# RFM2Pi_K16.net
KiCad netlist of a schematic drawn in EAGLE
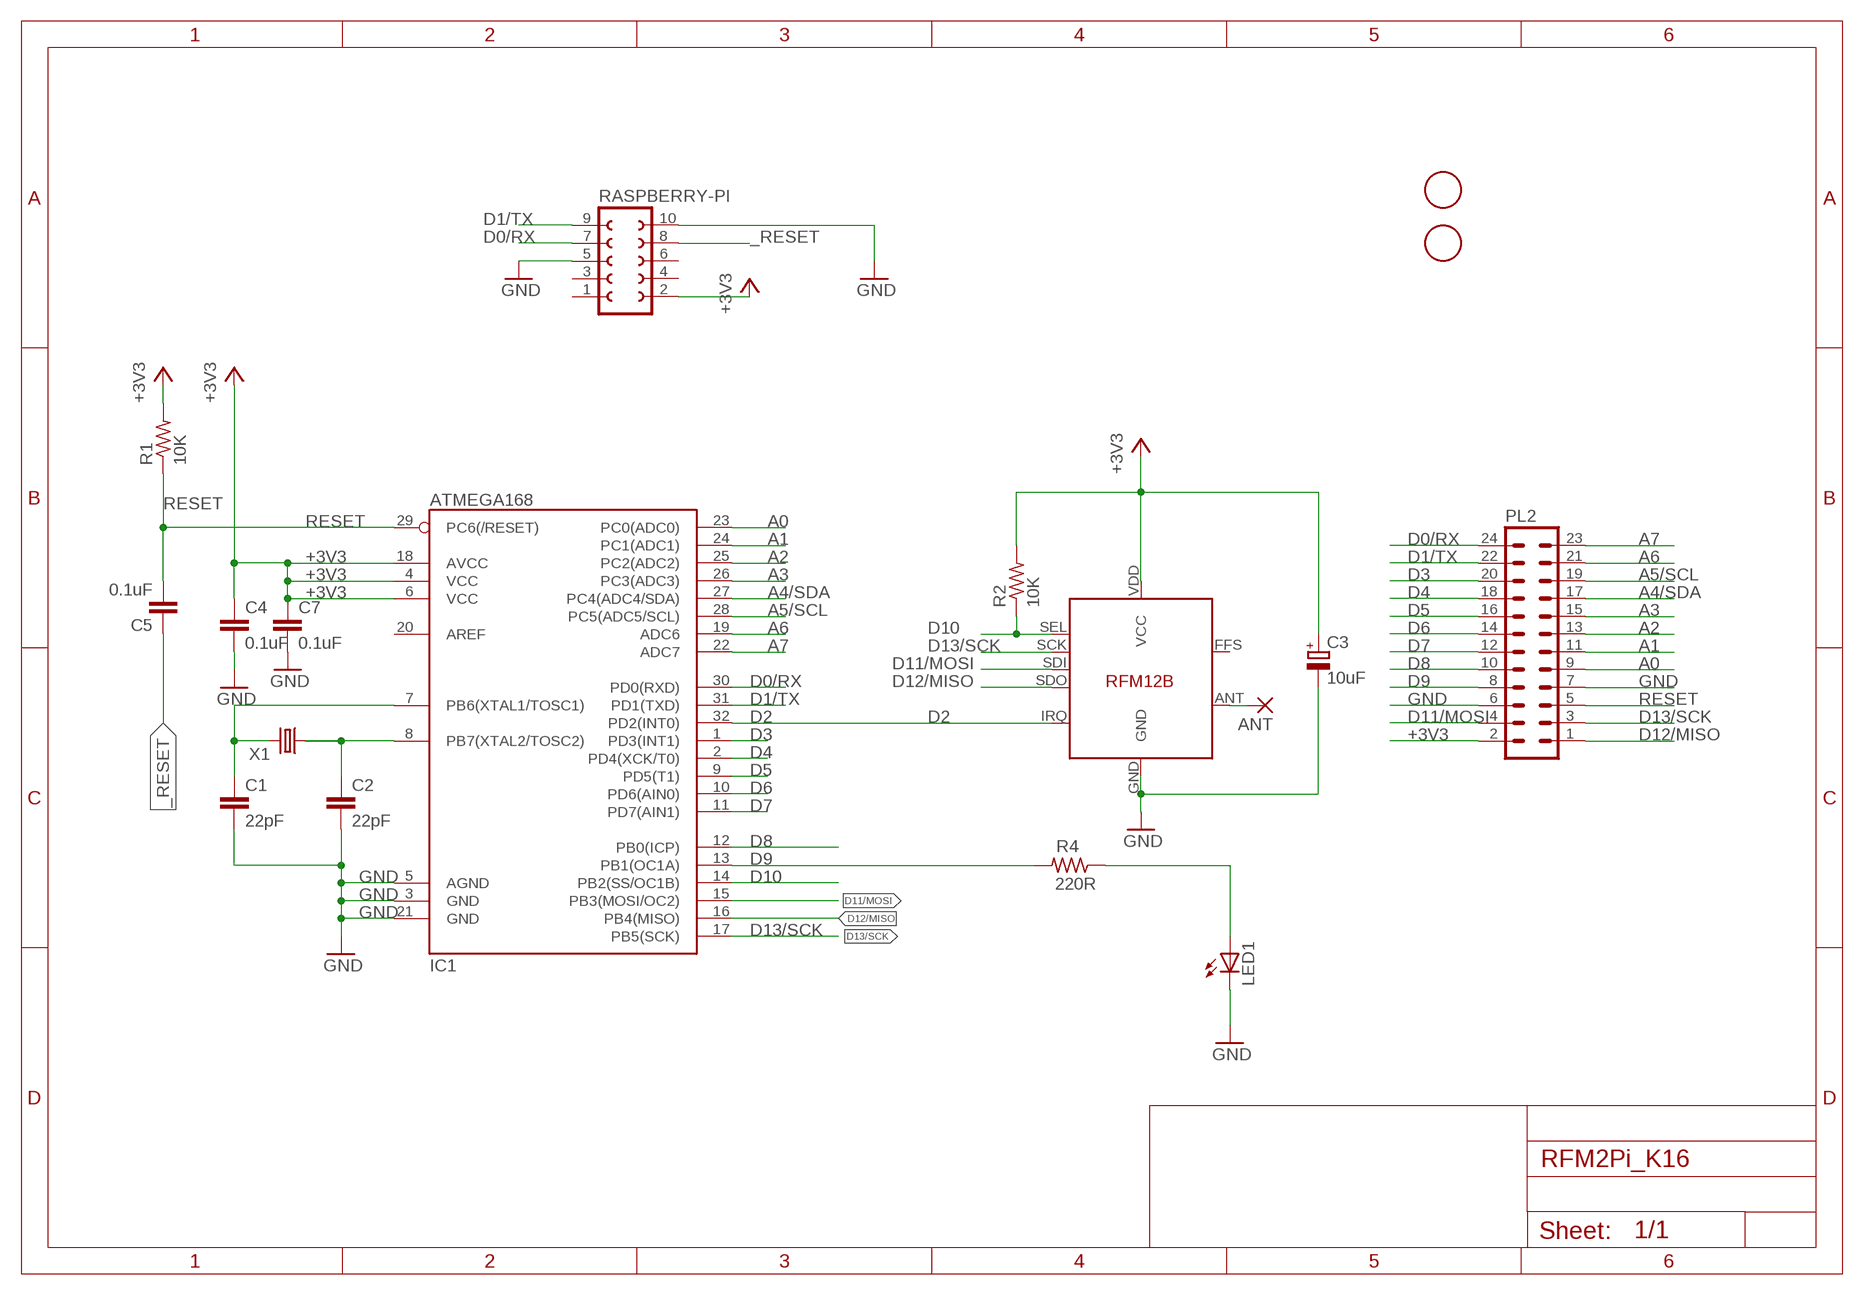
[diagram p0: schematic, sheet 1]

(export (version "E")
  (design (tool "Eeschema 10.0.6"))
  (components
    (comp (ref "ANT")
      (value "1,6/0,8")
      (footprint "eagle-import:1,6_0,8")
      (libsource (lib "eagle-import") (part "1,6/0,8"))
    )
    (comp (ref "C1")
      (value "22pF")
      (footprint "eagle-import:C0603")
      (libsource (lib "eagle-import") (part "C-EUC0603"))
    )
    (comp (ref "C2")
      (value "22pF")
      (footprint "eagle-import:C0603")
      (libsource (lib "eagle-import") (part "C-EUC0603"))
    )
    (comp (ref "C3")
      (value "10uF")
      (footprint "eagle-import:B_3528-21W")
      (libsource (lib "eagle-import") (part "CPOL-EUB/3528-21W"))
    )
    (comp (ref "C4")
      (value "0.1uF")
      (footprint "eagle-import:C0603")
      (libsource (lib "eagle-import") (part "C-EUC0603"))
    )
    (comp (ref "C5")
      (value "0.1uF")
      (footprint "eagle-import:C0603")
      (libsource (lib "eagle-import") (part "C-EUC0603"))
    )
    (comp (ref "C7")
      (value "0.1uF")
      (footprint "eagle-import:C0603")
      (libsource (lib "eagle-import") (part "resistor_C-EUC0603"))
    )
    (comp (ref "IC1")
      (value "ATMEGA168")
      (footprint "eagle-import:TQFP32-08")
      (libsource (lib "eagle-import") (part "ATMEGA168"))
    )
    (comp (ref "LED1")
      (value "LEDSML0603")
      (footprint "eagle-import:SML0603")
      (libsource (lib "eagle-import") (part "LEDSML0603"))
    )
    (comp (ref "PL2")
      (value "MA12-2")
      (footprint "eagle-import:MA12-2")
      (libsource (lib "eagle-import") (part "MA12-2"))
    )
    (comp (ref "R1")
      (value "10K")
      (footprint "eagle-import:R0603")
      (libsource (lib "eagle-import") (part "R-US_R0603"))
    )
    (comp (ref "R2")
      (value "10K")
      (footprint "eagle-import:R0603")
      (libsource (lib "eagle-import") (part "R-US_R0603"))
    )
    (comp (ref "R4")
      (value "220R")
      (footprint "eagle-import:R0603")
      (libsource (lib "eagle-import") (part "R-US_R0603"))
    )
    (comp (ref "RASPBERRY-PI")
      (value "FE05-2")
      (footprint "eagle-import:FE05-2")
      (libsource (lib "eagle-import") (part "FE05-2"))
    )
    (comp (ref "RFM12B")
      (value "RFM12B")
      (footprint "eagle-import:RFM12B")
      (libsource (lib "eagle-import") (part "RFM12B"))
    )
    (comp (ref "U$1")
      (value "FIDUCIAL")
      (footprint "eagle-import:FIDUCIAL_1MM")
      (libsource (lib "eagle-import") (part "FIDUCIAL"))
    )
    (comp (ref "U$2")
      (value "FIDUCIAL")
      (footprint "eagle-import:FIDUCIAL_1MM")
      (libsource (lib "eagle-import") (part "FIDUCIAL"))
    )
    (comp (ref "X1")
      (value "CRYSTALHC49US")
      (footprint "eagle-import:HC49US")
      (libsource (lib "eagle-import") (part "CRYSTALHC49US"))
    )
  )
  (nets
    (net (code "1") (name "+3V3") (class "Default")
      (node (ref "C3") (pin "+") (pinfunction "+_+") (pintype "passive"))
      (node (ref "C4") (pin "1") (pinfunction "1_1") (pintype "passive"))
      (node (ref "C7") (pin "1") (pinfunction "1_1") (pintype "passive"))
      (node (ref "IC1") (pin "18") (pinfunction "AVCC_18") (pintype "bidirectional"))
      (node (ref "IC1") (pin "4") (pinfunction "VCC_4") (pintype "bidirectional"))
      (node (ref "IC1") (pin "6") (pinfunction "VCC_6") (pintype "bidirectional"))
      (node (ref "PL2") (pin "2") (pinfunction "2_2") (pintype "passive"))
      (node (ref "R1") (pin "2") (pinfunction "2_2") (pintype "passive"))
      (node (ref "R2") (pin "2") (pinfunction "2_2") (pintype "passive"))
      (node (ref "RASPBERRY-PI") (pin "2") (pinfunction "2_2") (pintype "passive"))
      (node (ref "RFM12B") (pin "VDD") (pinfunction "VCC_VDD") (pintype "power_in"))
    )
    (net (code "2") (name "/A0") (class "Default")
      (node (ref "IC1") (pin "23") (pinfunction "PC0(ADC0)_23") (pintype "bidirectional"))
      (node (ref "PL2") (pin "9") (pinfunction "9_9") (pintype "passive"))
    )
    (net (code "3") (name "/A1") (class "Default")
      (node (ref "IC1") (pin "24") (pinfunction "PC1(ADC1)_24") (pintype "bidirectional"))
      (node (ref "PL2") (pin "11") (pinfunction "11_11") (pintype "passive"))
    )
    (net (code "4") (name "/A2") (class "Default")
      (node (ref "IC1") (pin "25") (pinfunction "PC2(ADC2)_25") (pintype "bidirectional"))
      (node (ref "PL2") (pin "13") (pinfunction "13_13") (pintype "passive"))
    )
    (net (code "5") (name "/A3") (class "Default")
      (node (ref "IC1") (pin "26") (pinfunction "PC3(ADC3)_26") (pintype "bidirectional"))
      (node (ref "PL2") (pin "15") (pinfunction "15_15") (pintype "passive"))
    )
    (net (code "6") (name "/A4{slash}SDA") (class "Default")
      (node (ref "IC1") (pin "27") (pinfunction "PC4(ADC4/SDA)_27") (pintype "bidirectional"))
      (node (ref "PL2") (pin "17") (pinfunction "17_17") (pintype "passive"))
    )
    (net (code "7") (name "/A5{slash}SCL") (class "Default")
      (node (ref "IC1") (pin "28") (pinfunction "PC5(ADC5/SCL)_28") (pintype "bidirectional"))
      (node (ref "PL2") (pin "19") (pinfunction "19_19") (pintype "passive"))
    )
    (net (code "8") (name "/A6") (class "Default")
      (node (ref "IC1") (pin "19") (pinfunction "ADC6_19") (pintype "bidirectional"))
      (node (ref "PL2") (pin "21") (pinfunction "21_21") (pintype "passive"))
    )
    (net (code "9") (name "/A7") (class "Default")
      (node (ref "IC1") (pin "22") (pinfunction "ADC7_22") (pintype "bidirectional"))
      (node (ref "PL2") (pin "23") (pinfunction "23_23") (pintype "passive"))
    )
    (net (code "10") (name "/D0{slash}RX") (class "Default")
      (node (ref "IC1") (pin "30") (pinfunction "PD0(RXD)_30") (pintype "bidirectional"))
      (node (ref "PL2") (pin "24") (pinfunction "24_24") (pintype "passive"))
      (node (ref "RASPBERRY-PI") (pin "7") (pinfunction "7_7") (pintype "passive"))
    )
    (net (code "11") (name "/D1{slash}TX") (class "Default")
      (node (ref "IC1") (pin "31") (pinfunction "PD1(TXD)_31") (pintype "bidirectional"))
      (node (ref "PL2") (pin "22") (pinfunction "22_22") (pintype "passive"))
      (node (ref "RASPBERRY-PI") (pin "9") (pinfunction "9_9") (pintype "passive"))
    )
    (net (code "12") (name "/D2") (class "Default")
      (node (ref "IC1") (pin "32") (pinfunction "PD2(INT0)_32") (pintype "bidirectional"))
      (node (ref "RFM12B") (pin "IRQ") (pinfunction "IRQ_IRQ") (pintype "open_collector"))
    )
    (net (code "13") (name "/D3") (class "Default")
      (node (ref "IC1") (pin "1") (pinfunction "PD3(INT1)_1") (pintype "bidirectional"))
      (node (ref "PL2") (pin "20") (pinfunction "20_20") (pintype "passive"))
    )
    (net (code "14") (name "/D4") (class "Default")
      (node (ref "IC1") (pin "2") (pinfunction "PD4(XCK/T0)_2") (pintype "bidirectional"))
      (node (ref "PL2") (pin "18") (pinfunction "18_18") (pintype "passive"))
    )
    (net (code "15") (name "/D5") (class "Default")
      (node (ref "IC1") (pin "9") (pinfunction "PD5(T1)_9") (pintype "bidirectional"))
      (node (ref "PL2") (pin "16") (pinfunction "16_16") (pintype "passive"))
    )
    (net (code "16") (name "/D6") (class "Default")
      (node (ref "IC1") (pin "10") (pinfunction "PD6(AIN0)_10") (pintype "bidirectional"))
      (node (ref "PL2") (pin "14") (pinfunction "14_14") (pintype "passive"))
    )
    (net (code "17") (name "/D7") (class "Default")
      (node (ref "IC1") (pin "11") (pinfunction "PD7(AIN1)_11") (pintype "bidirectional"))
      (node (ref "PL2") (pin "12") (pinfunction "12_12") (pintype "passive"))
    )
    (net (code "18") (name "/D8") (class "Default")
      (node (ref "IC1") (pin "12") (pinfunction "PB0(ICP)_12") (pintype "bidirectional"))
      (node (ref "PL2") (pin "10") (pinfunction "10_10") (pintype "passive"))
    )
    (net (code "19") (name "/D9") (class "Default")
      (node (ref "IC1") (pin "13") (pinfunction "PB1(OC1A)_13") (pintype "bidirectional"))
      (node (ref "PL2") (pin "8") (pinfunction "8_8") (pintype "passive"))
      (node (ref "R4") (pin "2") (pinfunction "2_2") (pintype "passive"))
    )
    (net (code "20") (name "/D10") (class "Default")
      (node (ref "IC1") (pin "14") (pinfunction "PB2(SS/OC1B)_14") (pintype "bidirectional"))
      (node (ref "R2") (pin "1") (pinfunction "1_1") (pintype "passive"))
      (node (ref "RFM12B") (pin "SEL") (pinfunction "SEL_SEL") (pintype "input"))
    )
    (net (code "21") (name "/RESET") (class "Default")
      (node (ref "C5") (pin "2") (pinfunction "2_2") (pintype "passive"))
      (node (ref "IC1") (pin "29") (pinfunction "PC6(/RESET)_29") (pintype "bidirectional"))
      (node (ref "PL2") (pin "5") (pinfunction "5_5") (pintype "passive"))
      (node (ref "R1") (pin "1") (pinfunction "1_1") (pintype "passive"))
    )
    (net (code "22") (name "D11{slash}MOSI") (class "Default")
      (node (ref "IC1") (pin "15") (pinfunction "PB3(MOSI/OC2)_15") (pintype "bidirectional"))
      (node (ref "PL2") (pin "4") (pinfunction "4_4") (pintype "passive"))
      (node (ref "RFM12B") (pin "SDI") (pinfunction "SDI_SDI") (pintype "input"))
    )
    (net (code "23") (name "D12{slash}MISO") (class "Default")
      (node (ref "IC1") (pin "16") (pinfunction "PB4(MISO)_16") (pintype "bidirectional"))
      (node (ref "PL2") (pin "1") (pinfunction "1_1") (pintype "passive"))
      (node (ref "RFM12B") (pin "SDO") (pinfunction "SDO_SDO") (pintype "output"))
    )
    (net (code "24") (name "D13{slash}SCK") (class "Default")
      (node (ref "IC1") (pin "17") (pinfunction "PB5(SCK)_17") (pintype "bidirectional"))
      (node (ref "PL2") (pin "3") (pinfunction "3_3") (pintype "passive"))
      (node (ref "RFM12B") (pin "SCK") (pinfunction "SCK_SCK") (pintype "input"))
    )
    (net (code "25") (name "GND") (class "Default")
      (node (ref "C1") (pin "2") (pinfunction "2_2") (pintype "passive"))
      (node (ref "C2") (pin "2") (pinfunction "2_2") (pintype "passive"))
      (node (ref "C3") (pin "-") (pinfunction "-_-") (pintype "passive"))
      (node (ref "C4") (pin "2") (pinfunction "2_2") (pintype "passive"))
      (node (ref "C7") (pin "2") (pinfunction "2_2") (pintype "passive"))
      (node (ref "IC1") (pin "21") (pinfunction "GND_21") (pintype "bidirectional"))
      (node (ref "IC1") (pin "3") (pinfunction "GND_3") (pintype "bidirectional"))
      (node (ref "IC1") (pin "5") (pinfunction "AGND_5") (pintype "bidirectional"))
      (node (ref "LED1") (pin "C") (pinfunction "C_C") (pintype "passive"))
      (node (ref "PL2") (pin "6") (pinfunction "6_6") (pintype "passive"))
      (node (ref "PL2") (pin "7") (pinfunction "7_7") (pintype "passive"))
      (node (ref "RASPBERRY-PI") (pin "10") (pinfunction "10_10") (pintype "passive"))
      (node (ref "RASPBERRY-PI") (pin "5") (pinfunction "5_5") (pintype "passive"))
      (node (ref "RFM12B") (pin "GND") (pinfunction "GND_GND") (pintype "power_in"))
    )
    (net (code "26") (name "Net-(ANT-P)") (class "Default")
      (node (ref "ANT") (pin "1") (pinfunction "P_1") (pintype "passive"))
      (node (ref "RFM12B") (pin "ANT") (pinfunction "ANT_ANT") (pintype "passive"))
    )
    (net (code "27") (name "Net-(IC1-PB6(XTAL1{slash}TOSC1))") (class "Default")
      (node (ref "C1") (pin "1") (pinfunction "1_1") (pintype "passive"))
      (node (ref "IC1") (pin "7") (pinfunction "PB6(XTAL1/TOSC1)_7") (pintype "bidirectional"))
      (node (ref "X1") (pin "2") (pinfunction "2_2") (pintype "passive"))
    )
    (net (code "28") (name "Net-(IC1-PB7(XTAL2{slash}TOSC2))") (class "Default")
      (node (ref "C2") (pin "1") (pinfunction "1_1") (pintype "passive"))
      (node (ref "IC1") (pin "8") (pinfunction "PB7(XTAL2/TOSC2)_8") (pintype "bidirectional"))
      (node (ref "X1") (pin "1") (pinfunction "1_1") (pintype "passive"))
    )
    (net (code "29") (name "Net-(LED1-PadA)") (class "Default")
      (node (ref "LED1") (pin "A") (pinfunction "A_A") (pintype "passive"))
      (node (ref "R4") (pin "1") (pinfunction "1_1") (pintype "passive"))
    )
    (net (code "30") (name "_RESET") (class "Default")
      (node (ref "C5") (pin "1") (pinfunction "1_1") (pintype "passive"))
      (node (ref "RASPBERRY-PI") (pin "8") (pinfunction "8_8") (pintype "passive"))
    )
    (net (code "31") (name "unconnected-(IC1-AREF-Pad20)") (class "Default")
      (node (ref "IC1") (pin "20") (pinfunction "AREF_20") (pintype "bidirectional"))
    )
    (net (code "32") (name "unconnected-(RASPBERRY-PI-Pad1)") (class "Default")
      (node (ref "RASPBERRY-PI") (pin "1") (pinfunction "1_1") (pintype "passive"))
    )
    (net (code "33") (name "unconnected-(RASPBERRY-PI-Pad3)") (class "Default")
      (node (ref "RASPBERRY-PI") (pin "3") (pinfunction "3_3") (pintype "passive"))
    )
    (net (code "34") (name "unconnected-(RASPBERRY-PI-Pad4)") (class "Default")
      (node (ref "RASPBERRY-PI") (pin "4") (pinfunction "4_4") (pintype "passive"))
    )
    (net (code "35") (name "unconnected-(RASPBERRY-PI-Pad6)") (class "Default")
      (node (ref "RASPBERRY-PI") (pin "6") (pinfunction "6_6") (pintype "passive"))
    )
    (net (code "36") (name "unconnected-(RFM12B-PadFFS)") (class "Default")
      (node (ref "RFM12B") (pin "FFS") (pinfunction "FFS_FFS") (pintype "bidirectional"))
    )
  )
)
